# pcbWithoutuE.net
KiCad netlist of a schematic drawn in EAGLE
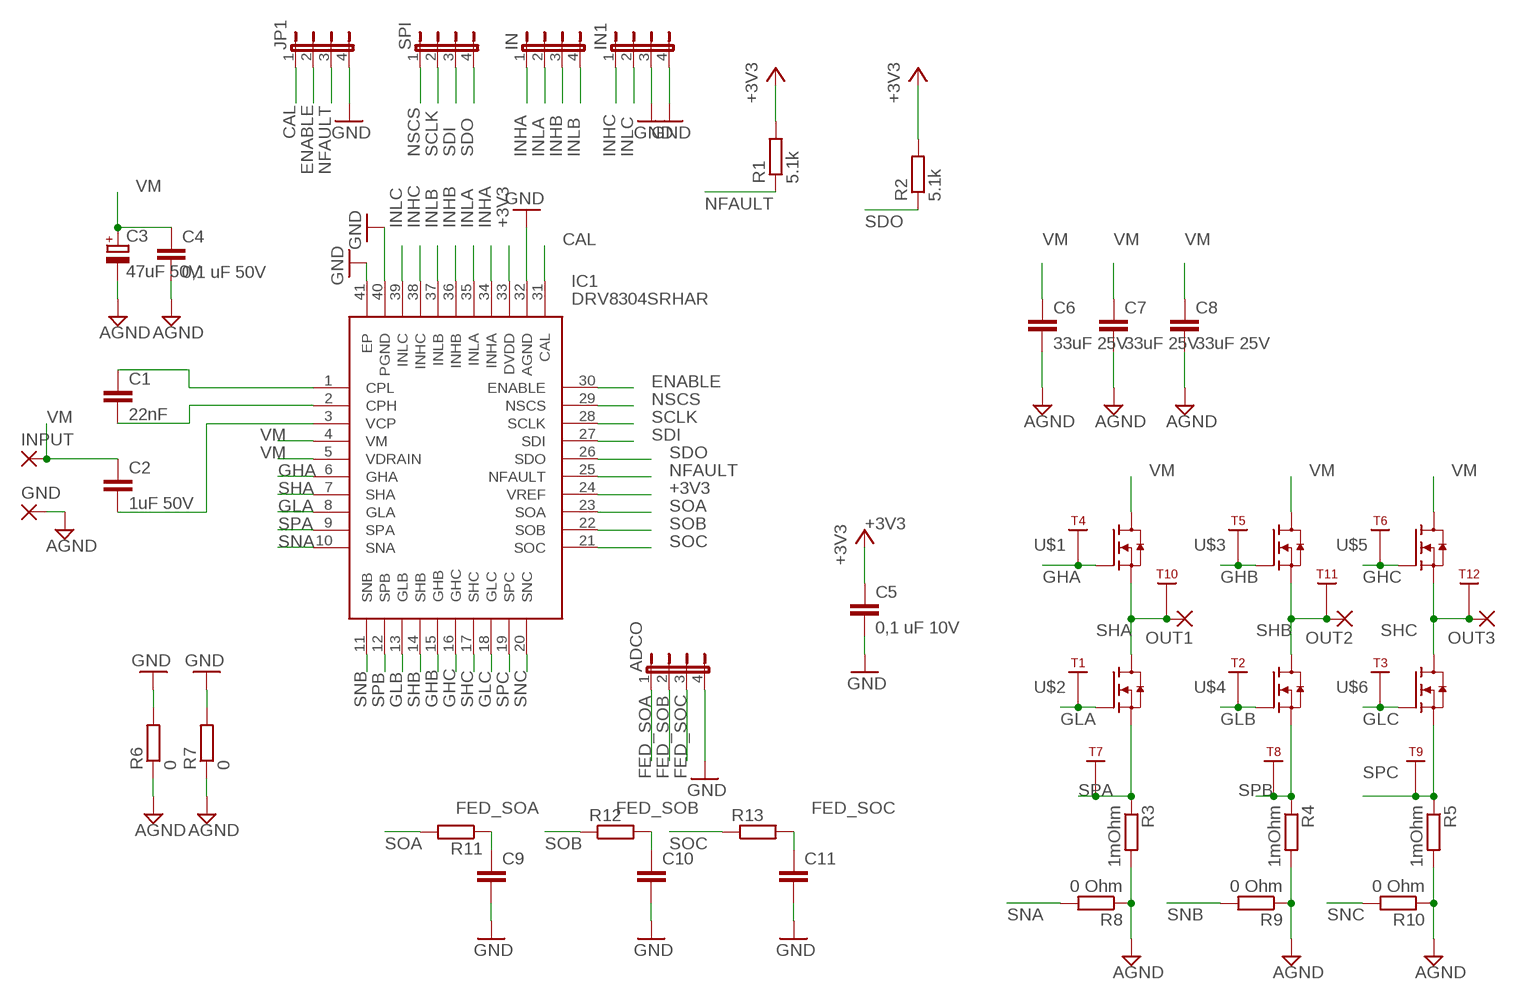
[diagram p0: schematic, sheet 1]

(export (version "E")
  (design (tool "Eeschema 10.0.6"))
  (components
    (comp (ref "ADCO")
      (value "JP4E")
      (footprint "eagle-import:JP4")
      (libsource (lib "eagle-import") (part "JP4E"))
    )
    (comp (ref "C1")
      (value "22nF")
      (footprint "eagle-import:C0805K")
      (libsource (lib "eagle-import") (part "C-EUC0805K"))
    )
    (comp (ref "C2")
      (value "1uF 50V")
      (footprint "eagle-import:C0805K")
      (libsource (lib "eagle-import") (part "C-EUC0805K"))
    )
    (comp (ref "C3")
      (value "47uF 50V")
      (footprint "eagle-import:E7,5-16")
      (libsource (lib "eagle-import") (part "CPOL-EUE7.5-16"))
    )
    (comp (ref "C4")
      (value "0,1 uF 50V")
      (footprint "eagle-import:C0805K")
      (libsource (lib "eagle-import") (part "C-EUC0805K"))
    )
    (comp (ref "C5")
      (value "0,1 uF 10V")
      (footprint "eagle-import:C0805K")
      (libsource (lib "eagle-import") (part "C-EUC0805K"))
    )
    (comp (ref "C6")
      (value "33uF 25V")
      (footprint "eagle-import:C1206K")
      (libsource (lib "eagle-import") (part "C-EUC1206K"))
    )
    (comp (ref "C7")
      (value "33uF 25V")
      (footprint "eagle-import:C1206K")
      (libsource (lib "eagle-import") (part "C-EUC1206K"))
    )
    (comp (ref "C8")
      (value "33uF 25V")
      (footprint "eagle-import:C1206K")
      (libsource (lib "eagle-import") (part "C-EUC1206K"))
    )
    (comp (ref "C9")
      (value "C-EUC0805")
      (footprint "eagle-import:C0805")
      (libsource (lib "eagle-import") (part "resistor_348_C-EUC0805"))
    )
    (comp (ref "C10")
      (value "C-EUC0805")
      (footprint "eagle-import:C0805")
      (libsource (lib "eagle-import") (part "resistor_348_C-EUC0805"))
    )
    (comp (ref "C11")
      (value "C-EUC0805")
      (footprint "eagle-import:C0805")
      (libsource (lib "eagle-import") (part "resistor_348_C-EUC0805"))
    )
    (comp (ref "GND")
      (value "3,17/1,3")
      (footprint "eagle-import:3,17_1,3")
      (libsource (lib "eagle-import") (part "3,17/1,3"))
    )
    (comp (ref "IC1")
      (value "DRV8304SRHAR")
      (footprint "eagle-import:QFN50P600X600X100-41N")
      (fields (field (name "MOUSER_PART_NUMBER") "595-DRV8304SRHAR"))
      (libsource (lib "eagle-import") (part "DRV8304SRHAR"))
    )
    (comp (ref "IN")
      (value "JP4E")
      (footprint "eagle-import:JP4")
      (libsource (lib "eagle-import") (part "JP4E"))
    )
    (comp (ref "IN1")
      (value "JP4E")
      (footprint "eagle-import:JP4")
      (libsource (lib "eagle-import") (part "JP4E"))
    )
    (comp (ref "INPUT")
      (value "3,17/1,3")
      (footprint "eagle-import:3,17_1,3")
      (libsource (lib "eagle-import") (part "3,17/1,3"))
    )
    (comp (ref "JP1")
      (value "JP4E")
      (footprint "eagle-import:JP4")
      (libsource (lib "eagle-import") (part "JP4E"))
    )
    (comp (ref "OUT1")
      (value "SMD2")
      (footprint "eagle-import:SMD1,27-2,54")
      (libsource (lib "eagle-import") (part "SMD2"))
    )
    (comp (ref "OUT2")
      (value "SMD2")
      (footprint "eagle-import:SMD1,27-2,54")
      (libsource (lib "eagle-import") (part "SMD2"))
    )
    (comp (ref "OUT3")
      (value "SMD2")
      (footprint "eagle-import:SMD1,27-2,54")
      (libsource (lib "eagle-import") (part "SMD2"))
    )
    (comp (ref "R1")
      (value "5.1k")
      (footprint "eagle-import:R0805")
      (libsource (lib "eagle-import") (part "R-EU_R0805"))
    )
    (comp (ref "R2")
      (value "5.1k")
      (footprint "eagle-import:R0805")
      (libsource (lib "eagle-import") (part "R-EU_R0805"))
    )
    (comp (ref "R3")
      (value "1mOhm")
      (footprint "eagle-import:1216")
      (libsource (lib "eagle-import") (part "R-EU_R1216_SHUNT"))
    )
    (comp (ref "R4")
      (value "1mOhm")
      (footprint "eagle-import:1216")
      (libsource (lib "eagle-import") (part "R-EU_R1216_SHUNT"))
    )
    (comp (ref "R5")
      (value "1mOhm")
      (footprint "eagle-import:1216")
      (libsource (lib "eagle-import") (part "R-EU_R1216_SHUNT"))
    )
    (comp (ref "R6")
      (value "0")
      (footprint "eagle-import:R0805W")
      (libsource (lib "eagle-import") (part "R-EU_R0805W"))
    )
    (comp (ref "R7")
      (value "0")
      (footprint "eagle-import:R0805W")
      (libsource (lib "eagle-import") (part "R-EU_R0805W"))
    )
    (comp (ref "R8")
      (value "0 Ohm")
      (footprint "eagle-import:R0603")
      (libsource (lib "eagle-import") (part "resistor_348_R-EU_R0603"))
    )
    (comp (ref "R9")
      (value "0 Ohm")
      (footprint "eagle-import:R0603")
      (libsource (lib "eagle-import") (part "resistor_348_R-EU_R0603"))
    )
    (comp (ref "R10")
      (value "0 Ohm")
      (footprint "eagle-import:R0603")
      (libsource (lib "eagle-import") (part "resistor_348_R-EU_R0603"))
    )
    (comp (ref "R11")
      (value "R-EU_R0805")
      (footprint "eagle-import:R0805")
      (libsource (lib "eagle-import") (part "resistor_348_R-EU_R0805"))
    )
    (comp (ref "R12")
      (value "R-EU_R0805")
      (footprint "eagle-import:R0805")
      (libsource (lib "eagle-import") (part "resistor_348_R-EU_R0805"))
    )
    (comp (ref "R13")
      (value "R-EU_R0805")
      (footprint "eagle-import:R0805")
      (libsource (lib "eagle-import") (part "resistor_348_R-EU_R0805"))
    )
    (comp (ref "SPI")
      (value "JP4E")
      (footprint "eagle-import:JP4")
      (libsource (lib "eagle-import") (part "JP4E"))
    )
    (comp (ref "T1")
      (value "TEST_POINT1593")
      (footprint "eagle-import:TURRET_TERMINAL_1593")
      (libsource (lib "eagle-import") (part "TEST_POINT1593"))
    )
    (comp (ref "T2")
      (value "TEST_POINT1593")
      (footprint "eagle-import:TURRET_TERMINAL_1593")
      (libsource (lib "eagle-import") (part "TEST_POINT1593"))
    )
    (comp (ref "T3")
      (value "TEST_POINT1593")
      (footprint "eagle-import:TURRET_TERMINAL_1593")
      (libsource (lib "eagle-import") (part "TEST_POINT1593"))
    )
    (comp (ref "T4")
      (value "TEST_POINT1593")
      (footprint "eagle-import:TURRET_TERMINAL_1593")
      (libsource (lib "eagle-import") (part "TEST_POINT1593"))
    )
    (comp (ref "T5")
      (value "TEST_POINT1593")
      (footprint "eagle-import:TURRET_TERMINAL_1593")
      (libsource (lib "eagle-import") (part "TEST_POINT1593"))
    )
    (comp (ref "T6")
      (value "TEST_POINT1593")
      (footprint "eagle-import:TURRET_TERMINAL_1593")
      (libsource (lib "eagle-import") (part "TEST_POINT1593"))
    )
    (comp (ref "T7")
      (value "TEST_POINT1593")
      (footprint "eagle-import:TURRET_TERMINAL_1593")
      (libsource (lib "eagle-import") (part "TEST_POINT1593"))
    )
    (comp (ref "T8")
      (value "TEST_POINT1593")
      (footprint "eagle-import:TURRET_TERMINAL_1593")
      (libsource (lib "eagle-import") (part "TEST_POINT1593"))
    )
    (comp (ref "T9")
      (value "TEST_POINT1593")
      (footprint "eagle-import:TURRET_TERMINAL_1593")
      (libsource (lib "eagle-import") (part "TEST_POINT1593"))
    )
    (comp (ref "T10")
      (value "TEST_POINT1593")
      (footprint "eagle-import:TURRET_TERMINAL_1593")
      (libsource (lib "eagle-import") (part "TEST_POINT1593"))
    )
    (comp (ref "T11")
      (value "TEST_POINT1593")
      (footprint "eagle-import:TURRET_TERMINAL_1593")
      (libsource (lib "eagle-import") (part "TEST_POINT1593"))
    )
    (comp (ref "T12")
      (value "TEST_POINT1593")
      (footprint "eagle-import:TURRET_TERMINAL_1593")
      (libsource (lib "eagle-import") (part "TEST_POINT1593"))
    )
    (comp (ref "U$1")
      (value "SIRA80DP-T1-RE3-CLASSIC")
      (footprint "eagle-import:SI7852ADPT1GE3")
      (libsource (lib "eagle-import") (part "SIRA80DP-T1-RE3-CLASSIC"))
    )
    (comp (ref "U$2")
      (value "SIRA80DP-T1-RE3-CLASSIC")
      (footprint "eagle-import:SI7852ADPT1GE3")
      (libsource (lib "eagle-import") (part "SIRA80DP-T1-RE3-CLASSIC"))
    )
    (comp (ref "U$3")
      (value "SIRA80DP-T1-RE3-CLASSIC")
      (footprint "eagle-import:SI7852ADPT1GE3")
      (libsource (lib "eagle-import") (part "SIRA80DP-T1-RE3-CLASSIC"))
    )
    (comp (ref "U$4")
      (value "SIRA80DP-T1-RE3-CLASSIC")
      (footprint "eagle-import:SI7852ADPT1GE3")
      (libsource (lib "eagle-import") (part "SIRA80DP-T1-RE3-CLASSIC"))
    )
    (comp (ref "U$5")
      (value "SIRA80DP-T1-RE3-CLASSIC")
      (footprint "eagle-import:SI7852ADPT1GE3")
      (libsource (lib "eagle-import") (part "SIRA80DP-T1-RE3-CLASSIC"))
    )
    (comp (ref "U$6")
      (value "SIRA80DP-T1-RE3-CLASSIC")
      (footprint "eagle-import:SI7852ADPT1GE3")
      (libsource (lib "eagle-import") (part "SIRA80DP-T1-RE3-CLASSIC"))
    )
  )
  (nets
    (net (code "1") (name "+3V3") (class "Default")
      (node (ref "C5") (pin "1") (pinfunction "1_1") (pintype "passive"))
      (node (ref "IC1") (pin "24") (pinfunction "VREF_24") (pintype "bidirectional"))
      (node (ref "IC1") (pin "33") (pinfunction "DVDD_33") (pintype "bidirectional"))
      (node (ref "R1") (pin "2") (pinfunction "2_2") (pintype "passive"))
      (node (ref "R2") (pin "2") (pinfunction "2_2") (pintype "passive"))
    )
    (net (code "2") (name "/CAL") (class "Default")
      (node (ref "IC1") (pin "31") (pinfunction "CAL_31") (pintype "bidirectional"))
      (node (ref "JP1") (pin "1") (pinfunction "1_1") (pintype "passive"))
    )
    (net (code "3") (name "/ENABLE") (class "Default")
      (node (ref "IC1") (pin "30") (pinfunction "ENABLE_30") (pintype "bidirectional"))
      (node (ref "JP1") (pin "2") (pinfunction "2_2") (pintype "passive"))
    )
    (net (code "4") (name "/FED_SOA") (class "Default")
      (node (ref "ADCO") (pin "1") (pinfunction "1_1") (pintype "passive"))
      (node (ref "C9") (pin "1") (pinfunction "1_1") (pintype "passive"))
      (node (ref "R11") (pin "1") (pinfunction "1_1") (pintype "passive"))
    )
    (net (code "5") (name "/FED_SOB") (class "Default")
      (node (ref "ADCO") (pin "2") (pinfunction "2_2") (pintype "passive"))
      (node (ref "C10") (pin "1") (pinfunction "1_1") (pintype "passive"))
      (node (ref "R12") (pin "2") (pinfunction "2_2") (pintype "passive"))
    )
    (net (code "6") (name "/FED_SOC") (class "Default")
      (node (ref "ADCO") (pin "3") (pinfunction "3_3") (pintype "passive"))
      (node (ref "C11") (pin "1") (pinfunction "1_1") (pintype "passive"))
      (node (ref "R13") (pin "2") (pinfunction "2_2") (pintype "passive"))
    )
    (net (code "7") (name "/GHA") (class "Default")
      (node (ref "IC1") (pin "6") (pinfunction "GHA_6") (pintype "bidirectional"))
      (node (ref "T4") (pin "1") (pinfunction "1_1") (pintype "passive"))
      (node (ref "U$1") (pin "4") (pinfunction "G_4") (pintype "passive"))
    )
    (net (code "8") (name "/GHB") (class "Default")
      (node (ref "IC1") (pin "15") (pinfunction "GHB_15") (pintype "bidirectional"))
      (node (ref "T5") (pin "1") (pinfunction "1_1") (pintype "passive"))
      (node (ref "U$3") (pin "4") (pinfunction "G_4") (pintype "passive"))
    )
    (net (code "9") (name "/GHC") (class "Default")
      (node (ref "IC1") (pin "16") (pinfunction "GHC_16") (pintype "bidirectional"))
      (node (ref "T6") (pin "1") (pinfunction "1_1") (pintype "passive"))
      (node (ref "U$5") (pin "4") (pinfunction "G_4") (pintype "passive"))
    )
    (net (code "10") (name "/GLA") (class "Default")
      (node (ref "IC1") (pin "8") (pinfunction "GLA_8") (pintype "bidirectional"))
      (node (ref "T1") (pin "1") (pinfunction "1_1") (pintype "passive"))
      (node (ref "U$2") (pin "4") (pinfunction "G_4") (pintype "passive"))
    )
    (net (code "11") (name "/GLB") (class "Default")
      (node (ref "IC1") (pin "13") (pinfunction "GLB_13") (pintype "bidirectional"))
      (node (ref "T2") (pin "1") (pinfunction "1_1") (pintype "passive"))
      (node (ref "U$4") (pin "4") (pinfunction "G_4") (pintype "passive"))
    )
    (net (code "12") (name "/GLC") (class "Default")
      (node (ref "IC1") (pin "18") (pinfunction "GLC_18") (pintype "bidirectional"))
      (node (ref "T3") (pin "1") (pinfunction "1_1") (pintype "passive"))
      (node (ref "U$6") (pin "4") (pinfunction "G_4") (pintype "passive"))
    )
    (net (code "13") (name "/INHA") (class "Default")
      (node (ref "IC1") (pin "34") (pinfunction "INHA_34") (pintype "bidirectional"))
      (node (ref "IN") (pin "1") (pinfunction "1_1") (pintype "passive"))
    )
    (net (code "14") (name "/INHB") (class "Default")
      (node (ref "IC1") (pin "36") (pinfunction "INHB_36") (pintype "bidirectional"))
      (node (ref "IN") (pin "3") (pinfunction "3_3") (pintype "passive"))
    )
    (net (code "15") (name "/INHC") (class "Default")
      (node (ref "IC1") (pin "38") (pinfunction "INHC_38") (pintype "bidirectional"))
      (node (ref "IN1") (pin "1") (pinfunction "1_1") (pintype "passive"))
    )
    (net (code "16") (name "/INLA") (class "Default")
      (node (ref "IC1") (pin "35") (pinfunction "INLA_35") (pintype "bidirectional"))
      (node (ref "IN") (pin "2") (pinfunction "2_2") (pintype "passive"))
    )
    (net (code "17") (name "/INLB") (class "Default")
      (node (ref "IC1") (pin "37") (pinfunction "INLB_37") (pintype "bidirectional"))
      (node (ref "IN") (pin "4") (pinfunction "4_4") (pintype "passive"))
    )
    (net (code "18") (name "/INLC") (class "Default")
      (node (ref "IC1") (pin "39") (pinfunction "INLC_39") (pintype "bidirectional"))
      (node (ref "IN1") (pin "2") (pinfunction "2_2") (pintype "passive"))
    )
    (net (code "19") (name "/NFAULT") (class "Default")
      (node (ref "IC1") (pin "25") (pinfunction "NFAULT_25") (pintype "bidirectional"))
      (node (ref "JP1") (pin "3") (pinfunction "3_3") (pintype "passive"))
      (node (ref "R1") (pin "1") (pinfunction "1_1") (pintype "passive"))
    )
    (net (code "20") (name "/NSCS") (class "Default")
      (node (ref "IC1") (pin "29") (pinfunction "NSCS_29") (pintype "bidirectional"))
      (node (ref "SPI") (pin "1") (pinfunction "1_1") (pintype "passive"))
    )
    (net (code "21") (name "/SCLK") (class "Default")
      (node (ref "IC1") (pin "28") (pinfunction "SCLK_28") (pintype "bidirectional"))
      (node (ref "SPI") (pin "2") (pinfunction "2_2") (pintype "passive"))
    )
    (net (code "22") (name "/SDI") (class "Default")
      (node (ref "IC1") (pin "27") (pinfunction "SDI_27") (pintype "bidirectional"))
      (node (ref "SPI") (pin "3") (pinfunction "3_3") (pintype "passive"))
    )
    (net (code "23") (name "/SDO") (class "Default")
      (node (ref "IC1") (pin "26") (pinfunction "SDO_26") (pintype "bidirectional"))
      (node (ref "R2") (pin "1") (pinfunction "1_1") (pintype "passive"))
      (node (ref "SPI") (pin "4") (pinfunction "4_4") (pintype "passive"))
    )
    (net (code "24") (name "/SHA") (class "Default")
      (node (ref "IC1") (pin "7") (pinfunction "SHA_7") (pintype "bidirectional"))
      (node (ref "OUT1") (pin "1") (pinfunction "P_1") (pintype "passive"))
      (node (ref "T10") (pin "1") (pinfunction "1_1") (pintype "passive"))
      (node (ref "U$1") (pin "1") (pinfunction "S_1") (pintype "passive"))
      (node (ref "U$1") (pin "2") (pinfunction "S_2") (pintype "passive"))
      (node (ref "U$1") (pin "3") (pinfunction "S_3") (pintype "passive"))
      (node (ref "U$2") (pin "10") (pinfunction "D_10") (pintype "passive"))
      (node (ref "U$2") (pin "11") (pinfunction "D_11") (pintype "passive"))
      (node (ref "U$2") (pin "5") (pinfunction "D_5") (pintype "passive"))
      (node (ref "U$2") (pin "6") (pinfunction "D_6") (pintype "passive"))
      (node (ref "U$2") (pin "7") (pinfunction "D_7") (pintype "passive"))
      (node (ref "U$2") (pin "8") (pinfunction "D_8") (pintype "passive"))
      (node (ref "U$2") (pin "9") (pinfunction "D_9") (pintype "passive"))
    )
    (net (code "25") (name "/SHB") (class "Default")
      (node (ref "IC1") (pin "14") (pinfunction "SHB_14") (pintype "bidirectional"))
      (node (ref "OUT2") (pin "1") (pinfunction "P_1") (pintype "passive"))
      (node (ref "T11") (pin "1") (pinfunction "1_1") (pintype "passive"))
      (node (ref "U$3") (pin "1") (pinfunction "S_1") (pintype "passive"))
      (node (ref "U$3") (pin "2") (pinfunction "S_2") (pintype "passive"))
      (node (ref "U$3") (pin "3") (pinfunction "S_3") (pintype "passive"))
      (node (ref "U$4") (pin "10") (pinfunction "D_10") (pintype "passive"))
      (node (ref "U$4") (pin "11") (pinfunction "D_11") (pintype "passive"))
      (node (ref "U$4") (pin "5") (pinfunction "D_5") (pintype "passive"))
      (node (ref "U$4") (pin "6") (pinfunction "D_6") (pintype "passive"))
      (node (ref "U$4") (pin "7") (pinfunction "D_7") (pintype "passive"))
      (node (ref "U$4") (pin "8") (pinfunction "D_8") (pintype "passive"))
      (node (ref "U$4") (pin "9") (pinfunction "D_9") (pintype "passive"))
    )
    (net (code "26") (name "/SHC") (class "Default")
      (node (ref "IC1") (pin "17") (pinfunction "SHC_17") (pintype "bidirectional"))
      (node (ref "OUT3") (pin "1") (pinfunction "P_1") (pintype "passive"))
      (node (ref "T12") (pin "1") (pinfunction "1_1") (pintype "passive"))
      (node (ref "U$5") (pin "1") (pinfunction "S_1") (pintype "passive"))
      (node (ref "U$5") (pin "2") (pinfunction "S_2") (pintype "passive"))
      (node (ref "U$5") (pin "3") (pinfunction "S_3") (pintype "passive"))
      (node (ref "U$6") (pin "10") (pinfunction "D_10") (pintype "passive"))
      (node (ref "U$6") (pin "11") (pinfunction "D_11") (pintype "passive"))
      (node (ref "U$6") (pin "5") (pinfunction "D_5") (pintype "passive"))
      (node (ref "U$6") (pin "6") (pinfunction "D_6") (pintype "passive"))
      (node (ref "U$6") (pin "7") (pinfunction "D_7") (pintype "passive"))
      (node (ref "U$6") (pin "8") (pinfunction "D_8") (pintype "passive"))
      (node (ref "U$6") (pin "9") (pinfunction "D_9") (pintype "passive"))
    )
    (net (code "27") (name "/SNA") (class "Default")
      (node (ref "IC1") (pin "10") (pinfunction "SNA_10") (pintype "bidirectional"))
      (node (ref "R8") (pin "2") (pinfunction "2_2") (pintype "passive"))
    )
    (net (code "28") (name "/SNB") (class "Default")
      (node (ref "IC1") (pin "11") (pinfunction "SNB_11") (pintype "bidirectional"))
      (node (ref "R9") (pin "2") (pinfunction "2_2") (pintype "passive"))
    )
    (net (code "29") (name "/SNC") (class "Default")
      (node (ref "IC1") (pin "20") (pinfunction "SNC_20") (pintype "bidirectional"))
      (node (ref "R10") (pin "2") (pinfunction "2_2") (pintype "passive"))
    )
    (net (code "30") (name "/SOA") (class "Default")
      (node (ref "IC1") (pin "23") (pinfunction "SOA_23") (pintype "bidirectional"))
      (node (ref "R11") (pin "2") (pinfunction "2_2") (pintype "passive"))
    )
    (net (code "31") (name "/SOB") (class "Default")
      (node (ref "IC1") (pin "22") (pinfunction "SOB_22") (pintype "bidirectional"))
      (node (ref "R12") (pin "1") (pinfunction "1_1") (pintype "passive"))
    )
    (net (code "32") (name "/SOC") (class "Default")
      (node (ref "IC1") (pin "21") (pinfunction "SOC_21") (pintype "bidirectional"))
      (node (ref "R13") (pin "1") (pinfunction "1_1") (pintype "passive"))
    )
    (net (code "33") (name "/SPA") (class "Default")
      (node (ref "IC1") (pin "9") (pinfunction "SPA_9") (pintype "bidirectional"))
      (node (ref "R3") (pin "P$1") (pinfunction "1_P$1") (pintype "passive"))
      (node (ref "R3") (pin "P$3") (pinfunction "1_P$3") (pintype "passive"))
      (node (ref "T7") (pin "1") (pinfunction "1_1") (pintype "passive"))
      (node (ref "U$2") (pin "1") (pinfunction "S_1") (pintype "passive"))
      (node (ref "U$2") (pin "2") (pinfunction "S_2") (pintype "passive"))
      (node (ref "U$2") (pin "3") (pinfunction "S_3") (pintype "passive"))
    )
    (net (code "34") (name "/SPB") (class "Default")
      (node (ref "IC1") (pin "12") (pinfunction "SPB_12") (pintype "bidirectional"))
      (node (ref "R4") (pin "P$1") (pinfunction "1_P$1") (pintype "passive"))
      (node (ref "R4") (pin "P$3") (pinfunction "1_P$3") (pintype "passive"))
      (node (ref "T8") (pin "1") (pinfunction "1_1") (pintype "passive"))
      (node (ref "U$4") (pin "1") (pinfunction "S_1") (pintype "passive"))
      (node (ref "U$4") (pin "2") (pinfunction "S_2") (pintype "passive"))
      (node (ref "U$4") (pin "3") (pinfunction "S_3") (pintype "passive"))
    )
    (net (code "35") (name "/SPC") (class "Default")
      (node (ref "IC1") (pin "19") (pinfunction "SPC_19") (pintype "bidirectional"))
      (node (ref "R5") (pin "P$1") (pinfunction "1_P$1") (pintype "passive"))
      (node (ref "R5") (pin "P$3") (pinfunction "1_P$3") (pintype "passive"))
      (node (ref "T9") (pin "1") (pinfunction "1_1") (pintype "passive"))
      (node (ref "U$6") (pin "1") (pinfunction "S_1") (pintype "passive"))
      (node (ref "U$6") (pin "2") (pinfunction "S_2") (pintype "passive"))
      (node (ref "U$6") (pin "3") (pinfunction "S_3") (pintype "passive"))
    )
    (net (code "36") (name "/VM") (class "Default")
      (node (ref "C2") (pin "1") (pinfunction "1_1") (pintype "passive"))
      (node (ref "C3") (pin "+") (pinfunction "+_+") (pintype "passive"))
      (node (ref "C4") (pin "1") (pinfunction "1_1") (pintype "passive"))
      (node (ref "C6") (pin "1") (pinfunction "1_1") (pintype "passive"))
      (node (ref "C7") (pin "1") (pinfunction "1_1") (pintype "passive"))
      (node (ref "C8") (pin "1") (pinfunction "1_1") (pintype "passive"))
      (node (ref "IC1") (pin "4") (pinfunction "VM_4") (pintype "bidirectional"))
      (node (ref "IC1") (pin "5") (pinfunction "VDRAIN_5") (pintype "bidirectional"))
      (node (ref "INPUT") (pin "1") (pinfunction "P_1") (pintype "passive"))
      (node (ref "U$1") (pin "10") (pinfunction "D_10") (pintype "passive"))
      (node (ref "U$1") (pin "11") (pinfunction "D_11") (pintype "passive"))
      (node (ref "U$1") (pin "5") (pinfunction "D_5") (pintype "passive"))
      (node (ref "U$1") (pin "6") (pinfunction "D_6") (pintype "passive"))
      (node (ref "U$1") (pin "7") (pinfunction "D_7") (pintype "passive"))
      (node (ref "U$1") (pin "8") (pinfunction "D_8") (pintype "passive"))
      (node (ref "U$1") (pin "9") (pinfunction "D_9") (pintype "passive"))
      (node (ref "U$3") (pin "10") (pinfunction "D_10") (pintype "passive"))
      (node (ref "U$3") (pin "11") (pinfunction "D_11") (pintype "passive"))
      (node (ref "U$3") (pin "5") (pinfunction "D_5") (pintype "passive"))
      (node (ref "U$3") (pin "6") (pinfunction "D_6") (pintype "passive"))
      (node (ref "U$3") (pin "7") (pinfunction "D_7") (pintype "passive"))
      (node (ref "U$3") (pin "8") (pinfunction "D_8") (pintype "passive"))
      (node (ref "U$3") (pin "9") (pinfunction "D_9") (pintype "passive"))
      (node (ref "U$5") (pin "10") (pinfunction "D_10") (pintype "passive"))
      (node (ref "U$5") (pin "11") (pinfunction "D_11") (pintype "passive"))
      (node (ref "U$5") (pin "5") (pinfunction "D_5") (pintype "passive"))
      (node (ref "U$5") (pin "6") (pinfunction "D_6") (pintype "passive"))
      (node (ref "U$5") (pin "7") (pinfunction "D_7") (pintype "passive"))
      (node (ref "U$5") (pin "8") (pinfunction "D_8") (pintype "passive"))
      (node (ref "U$5") (pin "9") (pinfunction "D_9") (pintype "passive"))
    )
    (net (code "37") (name "AGND") (class "Default")
      (node (ref "C3") (pin "-") (pinfunction "-_-") (pintype "passive"))
      (node (ref "C4") (pin "2") (pinfunction "2_2") (pintype "passive"))
      (node (ref "C6") (pin "2") (pinfunction "2_2") (pintype "passive"))
      (node (ref "C7") (pin "2") (pinfunction "2_2") (pintype "passive"))
      (node (ref "C8") (pin "2") (pinfunction "2_2") (pintype "passive"))
      (node (ref "GND") (pin "1") (pinfunction "P_1") (pintype "passive"))
      (node (ref "R10") (pin "1") (pinfunction "1_1") (pintype "passive"))
      (node (ref "R3") (pin "P$2") (pinfunction "2_P$2") (pintype "passive"))
      (node (ref "R3") (pin "P$4") (pinfunction "2_P$4") (pintype "passive"))
      (node (ref "R4") (pin "P$2") (pinfunction "2_P$2") (pintype "passive"))
      (node (ref "R4") (pin "P$4") (pinfunction "2_P$4") (pintype "passive"))
      (node (ref "R5") (pin "P$2") (pinfunction "2_P$2") (pintype "passive"))
      (node (ref "R5") (pin "P$4") (pinfunction "2_P$4") (pintype "passive"))
      (node (ref "R6") (pin "1") (pinfunction "1_1") (pintype "passive"))
      (node (ref "R7") (pin "1") (pinfunction "1_1") (pintype "passive"))
      (node (ref "R8") (pin "1") (pinfunction "1_1") (pintype "passive"))
      (node (ref "R9") (pin "1") (pinfunction "1_1") (pintype "passive"))
    )
    (net (code "38") (name "GND") (class "Default")
      (node (ref "ADCO") (pin "4") (pinfunction "4_4") (pintype "passive"))
      (node (ref "C10") (pin "2") (pinfunction "2_2") (pintype "passive"))
      (node (ref "C11") (pin "2") (pinfunction "2_2") (pintype "passive"))
      (node (ref "C5") (pin "2") (pinfunction "2_2") (pintype "passive"))
      (node (ref "C9") (pin "2") (pinfunction "2_2") (pintype "passive"))
      (node (ref "IC1") (pin "32") (pinfunction "AGND_32") (pintype "bidirectional"))
      (node (ref "IC1") (pin "40") (pinfunction "PGND_40") (pintype "bidirectional"))
      (node (ref "IC1") (pin "41") (pinfunction "EP_41") (pintype "bidirectional"))
      (node (ref "IN1") (pin "3") (pinfunction "3_3") (pintype "passive"))
      (node (ref "IN1") (pin "4") (pinfunction "4_4") (pintype "passive"))
      (node (ref "JP1") (pin "4") (pinfunction "4_4") (pintype "passive"))
      (node (ref "R6") (pin "2") (pinfunction "2_2") (pintype "passive"))
      (node (ref "R7") (pin "2") (pinfunction "2_2") (pintype "passive"))
    )
    (net (code "39") (name "Net-(IC1-CPH)") (class "Default")
      (node (ref "C1") (pin "2") (pinfunction "2_2") (pintype "passive"))
      (node (ref "IC1") (pin "2") (pinfunction "CPH_2") (pintype "bidirectional"))
    )
    (net (code "40") (name "Net-(IC1-CPL)") (class "Default")
      (node (ref "C1") (pin "1") (pinfunction "1_1") (pintype "passive"))
      (node (ref "IC1") (pin "1") (pinfunction "CPL_1") (pintype "bidirectional"))
    )
    (net (code "41") (name "Net-(IC1-VCP)") (class "Default")
      (node (ref "C2") (pin "2") (pinfunction "2_2") (pintype "passive"))
      (node (ref "IC1") (pin "3") (pinfunction "VCP_3") (pintype "bidirectional"))
    )
  )
)
